# Main.net
KiCad netlist of a schematic drawn in Altium Designer
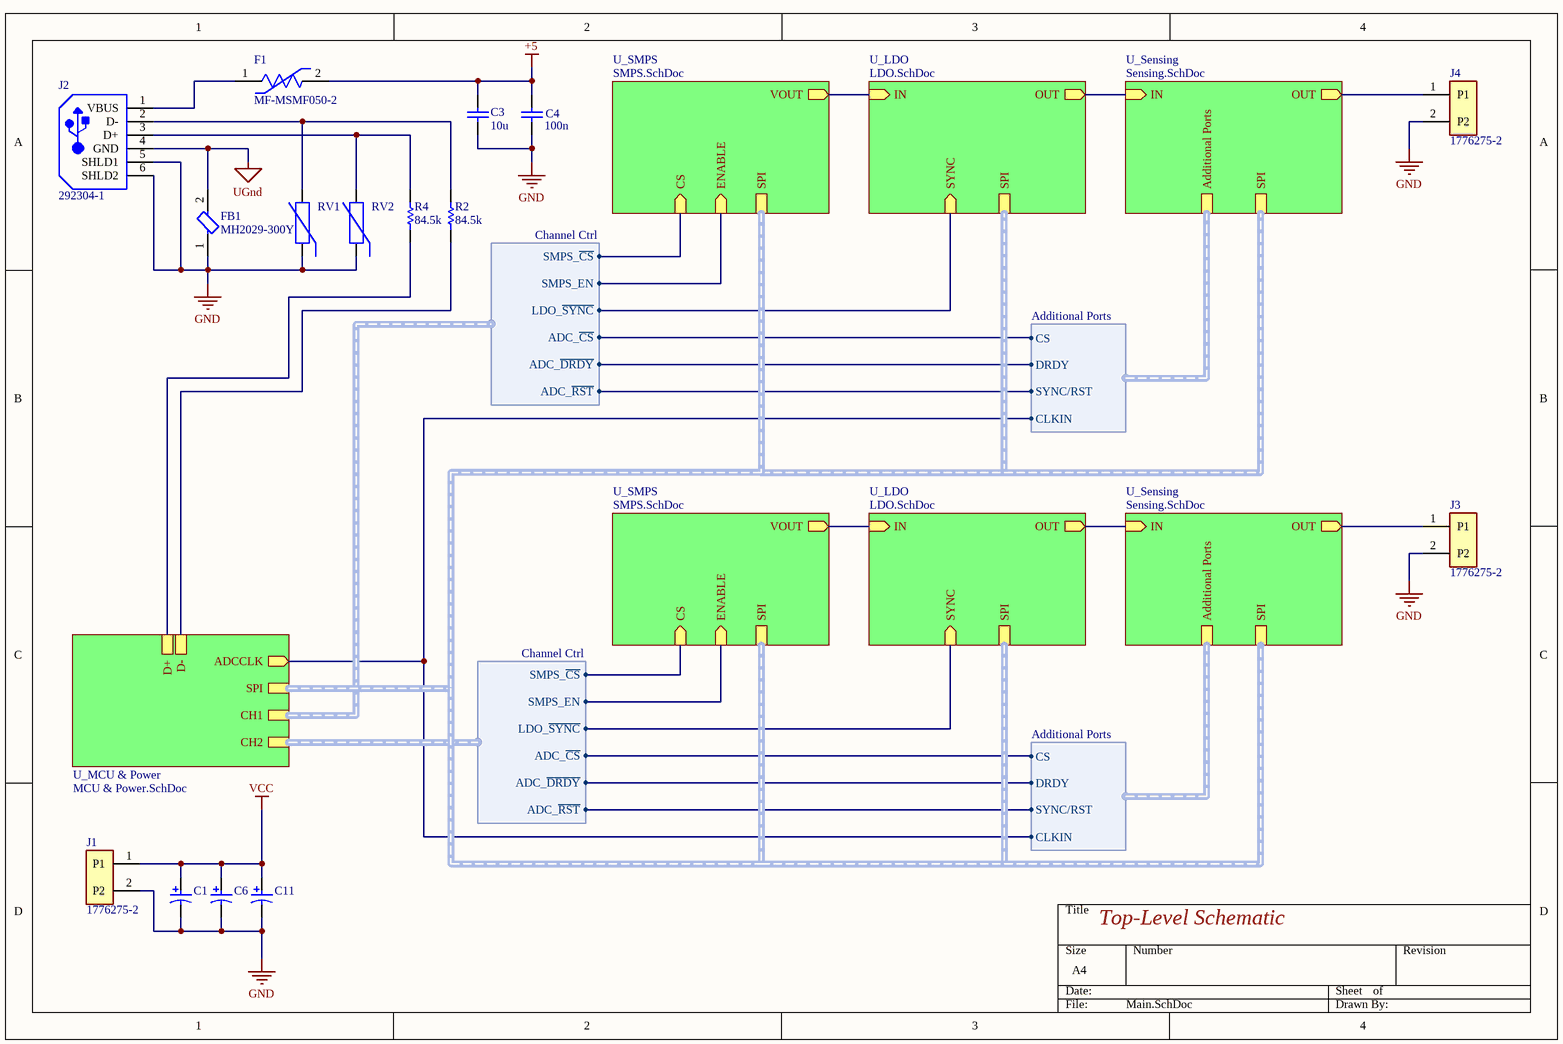
[diagram p0: Main.SchDoc]

(export (version "E")
  (design (tool "Eeschema 10.0.6"))
  (components
    (comp (ref "C1")
      (value "ECA-1JHG471")
      (footprint "CAPPR65-500-2000X1250X2200")
      (fields (field (name "MANUFACTURER") "Panasonic"))
      (libsource (lib "Altium Content Vault") (part "CAP-P-2"))
    )
    (comp (ref "C3")
      (value "10u")
      (footprint "CAPC3216X180X55LL20T30")
      (fields (field (name "MANUFACTURER") "Taiyo Yuden") (field (name "TOLERANCE") "±10%"))
      (libsource (lib "Altium Content Vault") (part "CAP-NP-2"))
    )
    (comp (ref "C4")
      (value "100n")
      (footprint "CAPC2013X145X50LL20T25")
      (fields (field (name "MANUFACTURER") "Kemet") (field (name "PART NUMBER") "C0805C104K3RALTU"))
      (libsource (lib "Altium Content Vault") (part "CAP"))
    )
    (comp (ref "C6")
      (value "ECA-1JHG471")
      (footprint "CAPPR65-500-2000X1250X2200")
      (fields (field (name "MANUFACTURER") "Panasonic"))
      (libsource (lib "Altium Content Vault") (part "CAP-P-2"))
    )
    (comp (ref "C11")
      (value "ECA-1JHG471")
      (footprint "CAPPR65-500-2000X1250X2200")
      (fields (field (name "MANUFACTURER") "Panasonic"))
      (libsource (lib "Altium Content Vault") (part "CAP-P-2"))
    )
    (comp (ref "F1")
      (value "MF-MSMF050-2")
      (footprint "FP-MF-MSMF050-2-MFG")
      (description "PTC RESET FUSE 15V 500MA 1812")
      (fields
        (field (name "MANUFACTURER") "Bourns")
        (field (name "OCTOPART") "https://octopart.com/mf-msmf050-2-bourns-28047")
      )
      (libsource (lib "Altium Content Vault") (part "fc31388045fc42ab786d6d00b506e9f"))
    )
    (comp (ref "FB1")
      (value "MH2029-300Y")
      (footprint "FP-MH2029-MFG")
      (description "FERRITE BEAD 30 OHM 0805 1LN")
      (fields
        (field (name "OCTOPART") "https://octopart.com/mh2029-300y-bourns-756929")
        (field (name "MANUFACTURER") "Bourns")
      )
      (libsource (lib "Altium Content Vault") (part "5f30dd21d616792df468990f7003faa"))
    )
    (comp (ref "J1")
      (value "1776275-2")
      (footprint "TE_1776275-2")
      (description "TERM BLOCK 2POS SIDE ENT 3.5MM")
      (fields (field (name "MF") "{'manufacturer': u'TE Connectivity'}"))
      (libsource (lib "") (part "1776275-2_1"))
    )
    (comp (ref "J2")
      (value "292304-1")
      (footprint "TECO-292304-1-4_V")
      (fields (field (name "MANUFACTURER") "TE Connectivity"))
      (libsource (lib "Altium Content Vault") (part "USB-4-2SHLD"))
    )
    (comp (ref "J3")
      (value "1776275-2")
      (footprint "TE_1776275-2")
      (description "TERM BLOCK 2POS SIDE ENT 3.5MM")
      (fields (field (name "MF") "{'manufacturer': u'TE Connectivity'}"))
      (libsource (lib "SnapEDA_Library") (part "1776275-2"))
    )
    (comp (ref "J4")
      (value "1776275-2")
      (footprint "TE_1776275-2")
      (description "TERM BLOCK 2POS SIDE ENT 3.5MM")
      (fields (field (name "MF") "{'manufacturer': u'TE Connectivity'}"))
      (libsource (lib "SnapEDA_Library") (part "1776275-2"))
    )
    (comp (ref "R2")
      (value "84.5k")
      (footprint "RESC2013X60X35NL10T20")
      (fields (field (name "MANUFACTURER") "Yageo") (field (name "PART NUMBER") "RC0805FR-0784K5L"))
      (libsource (lib "Altium Content Vault") (part "RES"))
    )
    (comp (ref "R4")
      (value "84.5k")
      (footprint "RESC2013X60X35NL10T20")
      (fields (field (name "MANUFACTURER") "Yageo") (field (name "PART NUMBER") "RC0805FR-0784K5L"))
      (libsource (lib "Altium Content Vault") (part "RES"))
    )
    (comp (ref "RV1")
      (value "CG0603MLC-05E")
      (footprint "BOUR-CG0603-2_V")
      (description "ESD Protector, 5 V Supply, -40 to 85 degC, 1.6 x 0.8 x 0.55 mm SMD, RoHS, Tape and Reel")
      (fields (field (name "MANUFACTURER") "Bourns"))
      (libsource (lib "Altium Content Vault") (part "BOUR-VSR-2"))
    )
    (comp (ref "RV2")
      (value "CG0603MLC-05E")
      (footprint "BOUR-CG0603-2_V")
      (description "ESD Protector, 5 V Supply, -40 to 85 degC, 1.6 x 0.8 x 0.55 mm SMD, RoHS, Tape and Reel")
      (fields (field (name "MANUFACTURER") "Bourns"))
      (libsource (lib "Altium Content Vault") (part "BOUR-VSR-2"))
    )
  )
  (nets
    (net (code "5") (name "+5") (class "Default")
      (node (ref "C3") (pin "2") (pinfunction "2_2") (pintype "passive"))
      (node (ref "C4") (pin "2") (pinfunction "2_2") (pintype "passive"))
      (node (ref "F1") (pin "2") (pinfunction "2_2") (pintype "passive"))
    )
    (net (code "9") (name "/D+") (class "Default")
      (node (ref "R4") (pin "1") (pinfunction "1_1") (pintype "passive"))
    )
    (net (code "10") (name "/D-") (class "Default")
      (node (ref "R2") (pin "1") (pinfunction "1_1") (pintype "passive"))
    )
    (net (code "13") (name "/OUT") (class "Default")
      (node (ref "J3") (pin "1") (pinfunction "P1_1") (pintype "passive"))
    )
    (net (code "15") (name "/OUT_2") (class "Default")
      (node (ref "J4") (pin "1") (pinfunction "P1_1") (pintype "passive"))
    )
    (net (code "24") (name "GND") (class "Default")
      (node (ref "C1") (pin "2") (pinfunction "2_2") (pintype "passive"))
      (node (ref "C11") (pin "2") (pinfunction "2_2") (pintype "passive"))
      (node (ref "C3") (pin "1") (pinfunction "1_1") (pintype "passive"))
      (node (ref "C4") (pin "1") (pinfunction "1_1") (pintype "passive"))
      (node (ref "C6") (pin "2") (pinfunction "2_2") (pintype "passive"))
      (node (ref "FB1") (pin "1") (pinfunction "1_1") (pintype "passive"))
      (node (ref "J1") (pin "2") (pinfunction "P2_2") (pintype "passive"))
      (node (ref "J2") (pin "5") (pinfunction "SHLD1_5") (pintype "passive"))
      (node (ref "J2") (pin "6") (pinfunction "SHLD2_6") (pintype "passive"))
      (node (ref "J3") (pin "2") (pinfunction "P2_2") (pintype "passive"))
      (node (ref "J4") (pin "2") (pinfunction "P2_2") (pintype "passive"))
      (node (ref "RV1") (pin "1") (pinfunction "1_1") (pintype "passive"))
      (node (ref "RV2") (pin "1") (pinfunction "1_1") (pintype "passive"))
    )
    (net (code "25") (name "Net-(J2-D+)") (class "Default")
      (node (ref "J2") (pin "3") (pinfunction "D+_3") (pintype "passive"))
      (node (ref "R4") (pin "2") (pinfunction "2_2") (pintype "passive"))
      (node (ref "RV2") (pin "2") (pinfunction "2_2") (pintype "passive"))
    )
    (net (code "26") (name "Net-(J2-D-)") (class "Default")
      (node (ref "J2") (pin "2") (pinfunction "D-_2") (pintype "passive"))
      (node (ref "R2") (pin "2") (pinfunction "2_2") (pintype "passive"))
      (node (ref "RV1") (pin "2") (pinfunction "2_2") (pintype "passive"))
    )
    (net (code "27") (name "Net-(J2-VBUS)") (class "Default")
      (node (ref "F1") (pin "1") (pinfunction "1_1") (pintype "passive"))
      (node (ref "J2") (pin "1") (pinfunction "VBUS_1") (pintype "passive"))
    )
    (net (code "28") (name "UGnd") (class "Default")
      (node (ref "FB1") (pin "2") (pinfunction "2_2") (pintype "passive"))
      (node (ref "J2") (pin "4") (pinfunction "GND_4") (pintype "passive"))
    )
    (net (code "29") (name "VCC") (class "Default")
      (node (ref "C1") (pin "1") (pinfunction "1_1") (pintype "passive"))
      (node (ref "C11") (pin "1") (pinfunction "1_1") (pintype "passive"))
      (node (ref "C6") (pin "1") (pinfunction "1_1") (pintype "passive"))
      (node (ref "J1") (pin "1") (pinfunction "P1_1") (pintype "passive"))
    )
  )
)
